# 1-Schematic.net
KiCad netlist of a schematic drawn in EasyEDA
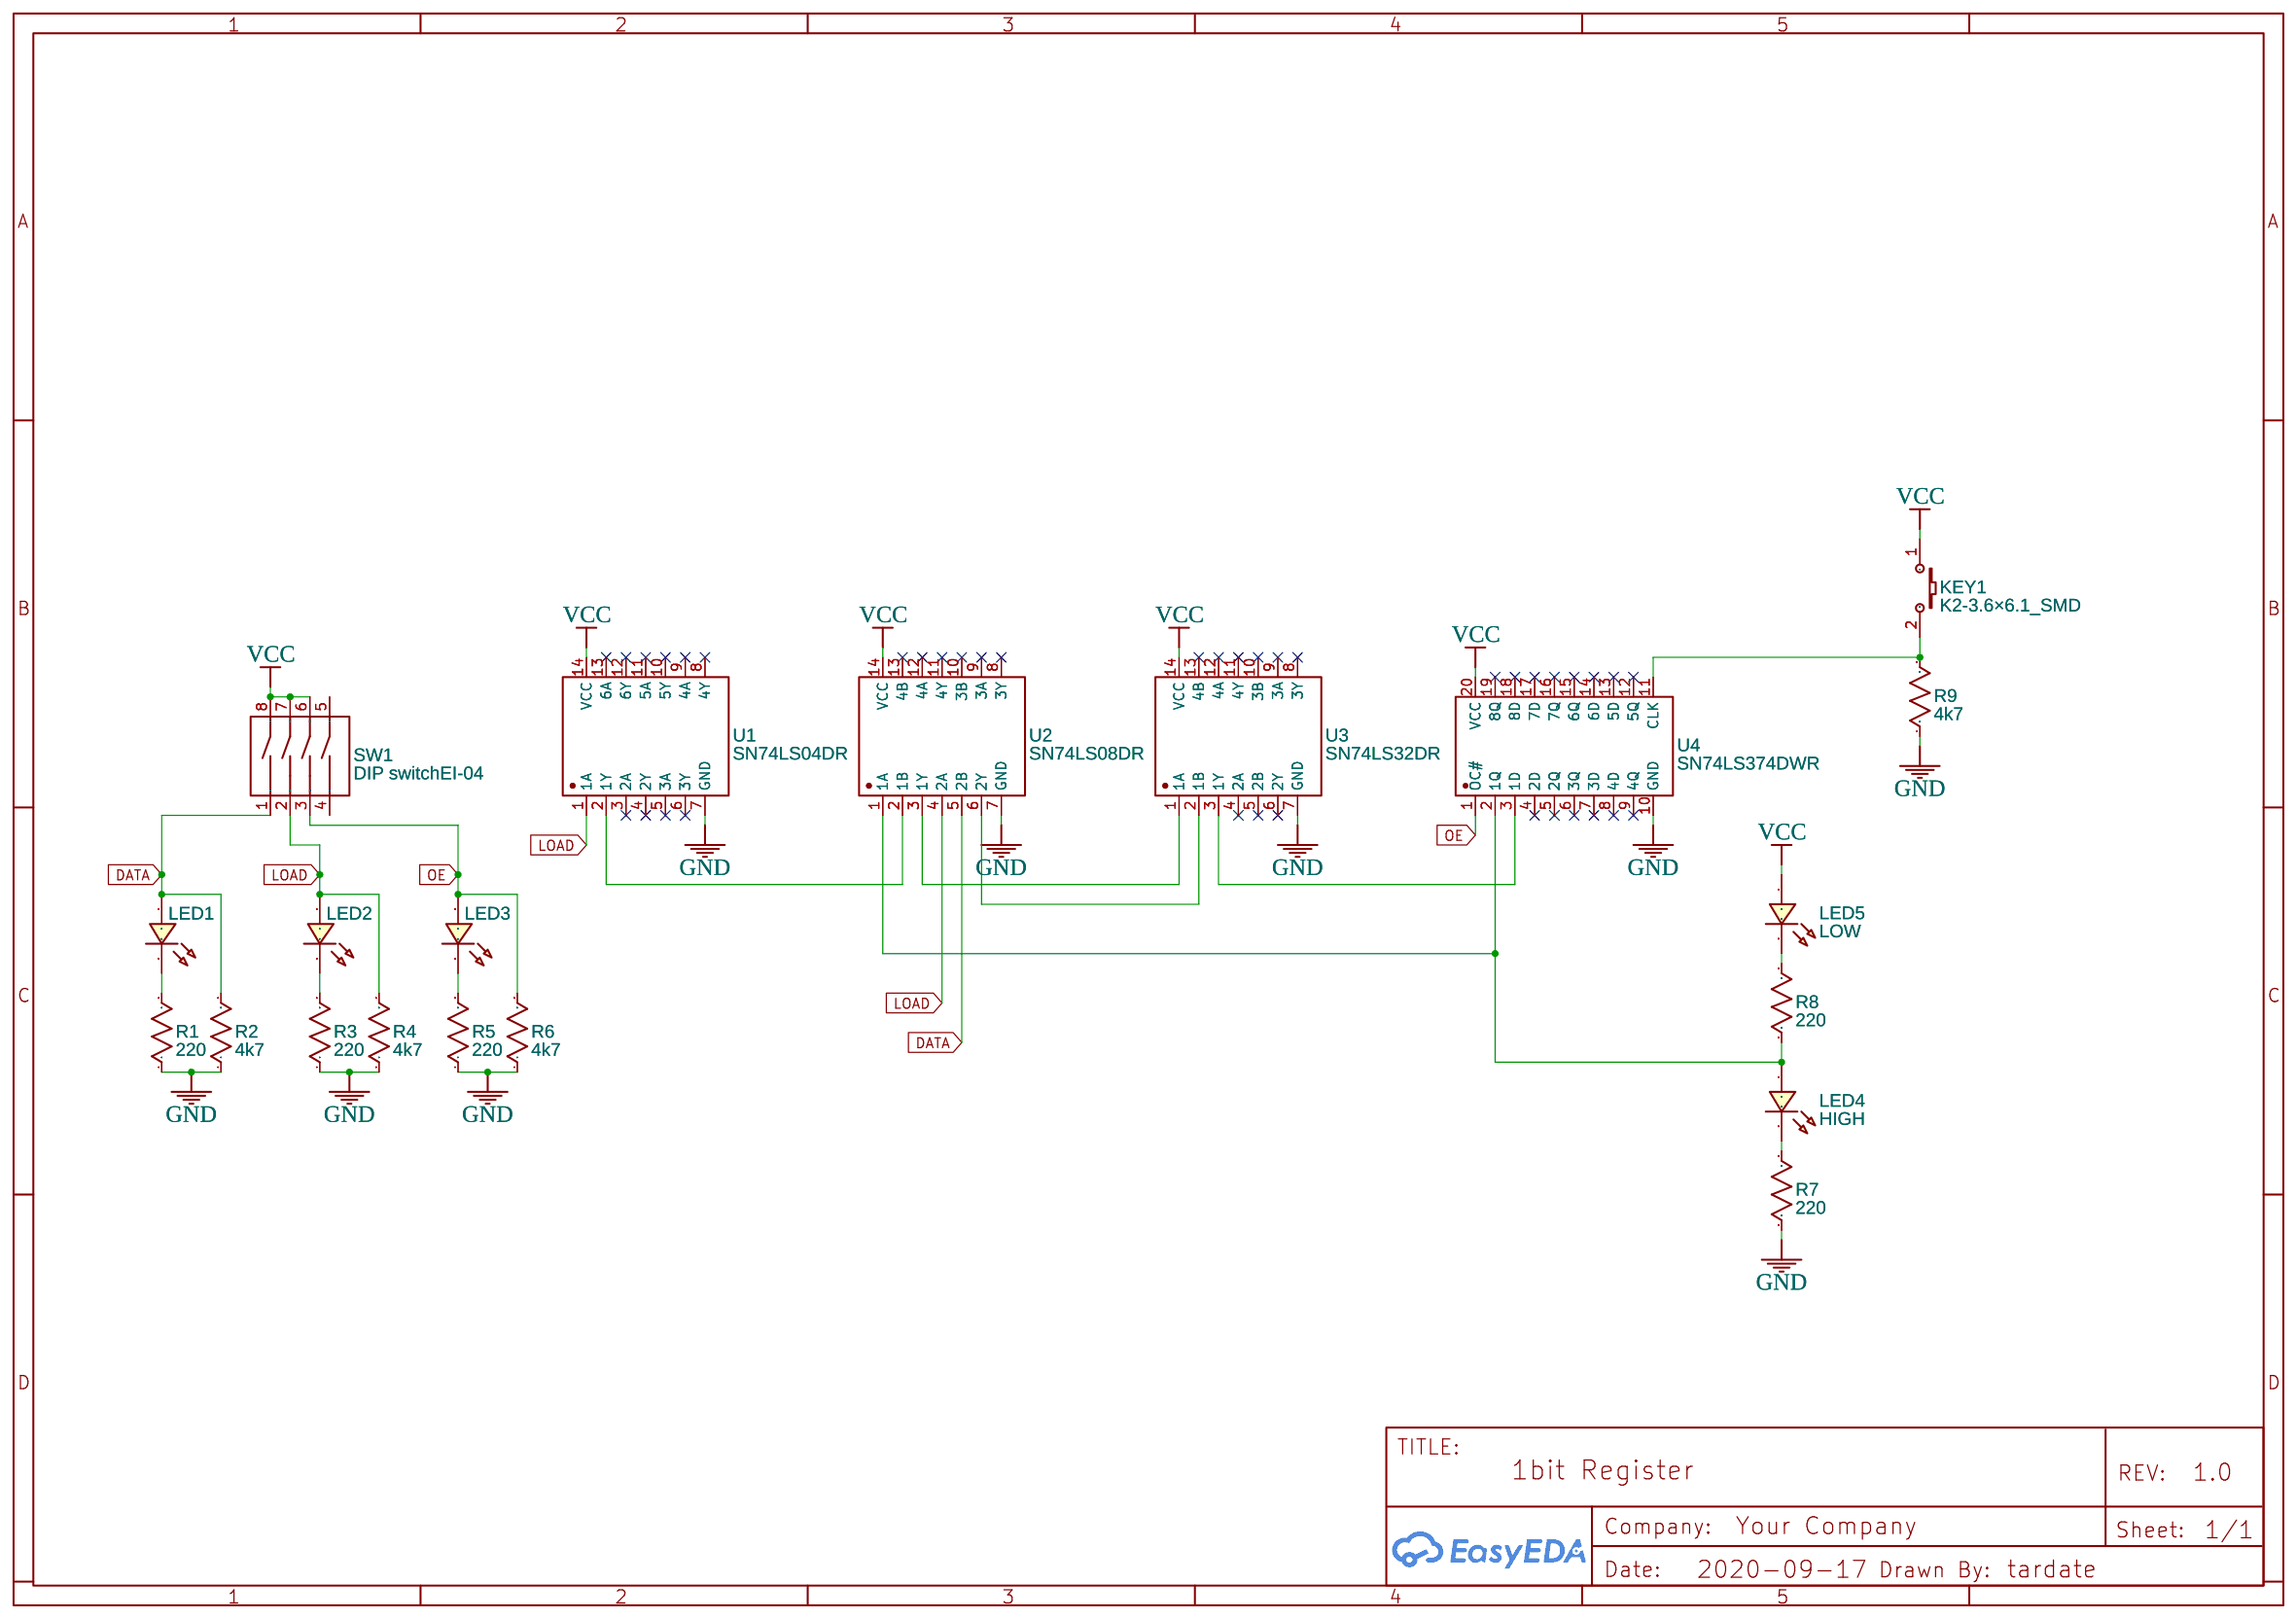
[diagram p0: schematic sheet]

(export (version "E")
  (design (tool "Eeschema 10.0.6"))
  (components
    (comp (ref "KEY1")
      (value "K2-3.6×6.1_SMD")
      (fields
        (field (name "BOM_Manufacturer Part") "K2-1107ST-A4SW-06")
        (field (name "BOM_Supplier Part") "C118141")
      )
      (libsource (lib "") (part "K2-3.6×6.1_SMD"))
    )
    (comp (ref "LED1")
      (value "LED-0603_R")
      (fields
        (field (name "BOM_Manufacturer Part") "19-217/R6C-AL1M2VY/3T")
        (field (name "BOM_Supplier Part") "C72044")
      )
      (libsource (lib "") (part "LED-0603_R"))
    )
    (comp (ref "LED2")
      (value "LED-0603_R")
      (fields
        (field (name "BOM_Manufacturer Part") "19-217/R6C-AL1M2VY/3T")
        (field (name "BOM_Supplier Part") "C72044")
      )
      (libsource (lib "") (part "LED-0603_R"))
    )
    (comp (ref "LED3")
      (value "LED-0603_R")
      (fields
        (field (name "BOM_Manufacturer Part") "19-217/R6C-AL1M2VY/3T")
        (field (name "BOM_Supplier Part") "C72044")
      )
      (libsource (lib "") (part "LED-0603_R"))
    )
    (comp (ref "LED4")
      (value "HIGH")
      (fields
        (field (name "BOM_Manufacturer Part") "19-217/R6C-AL1M2VY/3T")
        (field (name "BOM_Supplier Part") "C72044")
      )
      (libsource (lib "") (part "LED-0603_R"))
    )
    (comp (ref "LED5")
      (value "LOW")
      (fields
        (field (name "BOM_Manufacturer Part") "19-217/R6C-AL1M2VY/3T")
        (field (name "BOM_Supplier Part") "C72044")
      )
      (libsource (lib "") (part "LED-0603_R"))
    )
    (comp (ref "R1") (value "220") (libsource (lib "") (part "R_0603_US")))
    (comp (ref "R2") (value "4k7") (libsource (lib "") (part "R_0603_US")))
    (comp (ref "R3") (value "220") (libsource (lib "") (part "R_0603_US")))
    (comp (ref "R4") (value "4k7") (libsource (lib "") (part "R_0603_US")))
    (comp (ref "R5") (value "220") (libsource (lib "") (part "R_0603_US")))
    (comp (ref "R6") (value "4k7") (libsource (lib "") (part "R_0603_US")))
    (comp (ref "R7") (value "220") (libsource (lib "") (part "R_0603_US")))
    (comp (ref "R8") (value "220") (libsource (lib "") (part "R_0603_US")))
    (comp (ref "R9") (value "4k7") (libsource (lib "") (part "R_0603_US")))
    (comp (ref "SW1")
      (value "DIP switchEI-04")
      (fields (field (name "BOM_Supplier Part") "C99987"))
      (libsource (lib "") (part "DIP switchEI-04"))
    )
    (comp (ref "U1")
      (value "SN74LS04DR")
      (fields (field (name "BOM_Supplier Part") "C6796"))
      (libsource (lib "") (part "SN74LS04DR"))
    )
    (comp (ref "U2")
      (value "SN74LS08DR")
      (fields (field (name "BOM_Supplier Part") "C6802"))
      (libsource (lib "") (part "SN74LS08DR"))
    )
    (comp (ref "U3")
      (value "SN74LS32DR")
      (fields (field (name "BOM_Supplier Part") "C116812"))
      (libsource (lib "") (part "SN74LS32DR"))
    )
    (comp (ref "U4")
      (value "SN74LS374DWR")
      (fields (field (name "BOM_Supplier Part") "C7763"))
      (libsource (lib "") (part "SN74LS374DWR"))
    )
  )
  (nets
    (net (code "1") (name "DATA") (class "Default")
      (node (ref "LED1") (pin "1") (pinfunction "1_1") (pintype "unspecified"))
      (node (ref "R2") (pin "2") (pinfunction "2_2") (pintype "unspecified"))
      (node (ref "SW1") (pin "1") (pinfunction "1_1") (pintype "unspecified"))
      (node (ref "U2") (pin "5") (pinfunction "2B_5") (pintype "unspecified"))
    )
    (net (code "2") (name "GND") (class "Default")
      (node (ref "R1") (pin "1") (pinfunction "1_1") (pintype "unspecified"))
      (node (ref "R2") (pin "1") (pinfunction "1_1") (pintype "unspecified"))
      (node (ref "R3") (pin "1") (pinfunction "1_1") (pintype "unspecified"))
      (node (ref "R4") (pin "1") (pinfunction "1_1") (pintype "unspecified"))
      (node (ref "R5") (pin "1") (pinfunction "1_1") (pintype "unspecified"))
      (node (ref "R6") (pin "1") (pinfunction "1_1") (pintype "unspecified"))
      (node (ref "R7") (pin "1") (pinfunction "1_1") (pintype "unspecified"))
      (node (ref "R9") (pin "1") (pinfunction "1_1") (pintype "unspecified"))
      (node (ref "U1") (pin "7") (pinfunction "GND_7") (pintype "unspecified"))
      (node (ref "U2") (pin "7") (pinfunction "GND_7") (pintype "unspecified"))
      (node (ref "U3") (pin "7") (pinfunction "GND_7") (pintype "unspecified"))
      (node (ref "U4") (pin "10") (pinfunction "GND_10") (pintype "unspecified"))
    )
    (net (code "3") (name "LOAD") (class "Default")
      (node (ref "LED2") (pin "1") (pinfunction "1_1") (pintype "unspecified"))
      (node (ref "R4") (pin "2") (pinfunction "2_2") (pintype "unspecified"))
      (node (ref "SW1") (pin "2") (pinfunction "2_2") (pintype "unspecified"))
      (node (ref "U1") (pin "1") (pinfunction "1A_1") (pintype "unspecified"))
      (node (ref "U2") (pin "4") (pinfunction "2A_4") (pintype "unspecified"))
    )
    (net (code "4") (name "Net-(LED1-Pad2)") (class "Default")
      (node (ref "LED1") (pin "2") (pinfunction "2_2") (pintype "unspecified"))
      (node (ref "R1") (pin "2") (pinfunction "2_2") (pintype "unspecified"))
    )
    (net (code "5") (name "Net-(LED2-Pad2)") (class "Default")
      (node (ref "LED2") (pin "2") (pinfunction "2_2") (pintype "unspecified"))
      (node (ref "R3") (pin "2") (pinfunction "2_2") (pintype "unspecified"))
    )
    (net (code "6") (name "Net-(LED3-Pad2)") (class "Default")
      (node (ref "LED3") (pin "2") (pinfunction "2_2") (pintype "unspecified"))
      (node (ref "R5") (pin "2") (pinfunction "2_2") (pintype "unspecified"))
    )
    (net (code "7") (name "Net-(LED4-Pad2)") (class "Default")
      (node (ref "LED4") (pin "2") (pinfunction "2_2") (pintype "unspecified"))
      (node (ref "R7") (pin "2") (pinfunction "2_2") (pintype "unspecified"))
    )
    (net (code "8") (name "Net-(LED5-Pad2)") (class "Default")
      (node (ref "LED5") (pin "2") (pinfunction "2_2") (pintype "unspecified"))
      (node (ref "R8") (pin "2") (pinfunction "2_2") (pintype "unspecified"))
    )
    (net (code "9") (name "Net-(U1-1Y)") (class "Default")
      (node (ref "U1") (pin "2") (pinfunction "1Y_2") (pintype "unspecified"))
      (node (ref "U2") (pin "2") (pinfunction "1B_2") (pintype "unspecified"))
    )
    (net (code "10") (name "Net-(U2-1A)") (class "Default")
      (node (ref "LED4") (pin "1") (pinfunction "1_1") (pintype "unspecified"))
      (node (ref "R8") (pin "1") (pinfunction "1_1") (pintype "unspecified"))
      (node (ref "U2") (pin "1") (pinfunction "1A_1") (pintype "unspecified"))
      (node (ref "U4") (pin "2") (pinfunction "1Q_2") (pintype "unspecified"))
    )
    (net (code "11") (name "Net-(U2-1Y)") (class "Default")
      (node (ref "U2") (pin "3") (pinfunction "1Y_3") (pintype "unspecified"))
      (node (ref "U3") (pin "1") (pinfunction "1A_1") (pintype "unspecified"))
    )
    (net (code "12") (name "Net-(U2-2Y)") (class "Default")
      (node (ref "U2") (pin "6") (pinfunction "2Y_6") (pintype "unspecified"))
      (node (ref "U3") (pin "2") (pinfunction "1B_2") (pintype "unspecified"))
    )
    (net (code "13") (name "Net-(U3-1Y)") (class "Default")
      (node (ref "U3") (pin "3") (pinfunction "1Y_3") (pintype "unspecified"))
      (node (ref "U4") (pin "3") (pinfunction "1D_3") (pintype "unspecified"))
    )
    (net (code "14") (name "Net-(U4-CLK)") (class "Default")
      (node (ref "KEY1") (pin "2") (pinfunction "2_2") (pintype "unspecified"))
      (node (ref "R9") (pin "2") (pinfunction "2_2") (pintype "unspecified"))
      (node (ref "U4") (pin "11") (pinfunction "CLK_11") (pintype "unspecified"))
    )
    (net (code "15") (name "OE") (class "Default")
      (node (ref "LED3") (pin "1") (pinfunction "1_1") (pintype "unspecified"))
      (node (ref "R6") (pin "2") (pinfunction "2_2") (pintype "unspecified"))
      (node (ref "SW1") (pin "3") (pinfunction "3_3") (pintype "unspecified"))
      (node (ref "U4") (pin "1") (pinfunction "OC#_1") (pintype "unspecified"))
    )
    (net (code "16") (name "VCC") (class "Default")
      (node (ref "KEY1") (pin "1") (pinfunction "1_1") (pintype "unspecified"))
      (node (ref "LED5") (pin "1") (pinfunction "1_1") (pintype "unspecified"))
      (node (ref "SW1") (pin "6") (pinfunction "6_6") (pintype "unspecified"))
      (node (ref "SW1") (pin "7") (pinfunction "7_7") (pintype "unspecified"))
      (node (ref "SW1") (pin "8") (pinfunction "8_8") (pintype "unspecified"))
      (node (ref "U1") (pin "14") (pinfunction "VCC_14") (pintype "unspecified"))
      (node (ref "U2") (pin "14") (pinfunction "VCC_14") (pintype "unspecified"))
      (node (ref "U3") (pin "14") (pinfunction "VCC_14") (pintype "unspecified"))
      (node (ref "U4") (pin "20") (pinfunction "VCC_20") (pintype "unspecified"))
    )
    (net (code "17") (name "unconnected-(SW1-Pad4)") (class "Default")
      (node (ref "SW1") (pin "4") (pinfunction "4_4") (pintype "unspecified"))
    )
    (net (code "18") (name "unconnected-(SW1-Pad5)") (class "Default")
      (node (ref "SW1") (pin "5") (pinfunction "5_5") (pintype "unspecified"))
    )
    (net (code "19") (name "unconnected-(U1-2A-Pad3)") (class "Default")
      (node (ref "U1") (pin "3") (pinfunction "2A_3") (pintype "unspecified+no_connect"))
    )
    (net (code "20") (name "unconnected-(U1-2Y-Pad4)") (class "Default")
      (node (ref "U1") (pin "4") (pinfunction "2Y_4") (pintype "unspecified+no_connect"))
    )
    (net (code "21") (name "unconnected-(U1-3A-Pad5)") (class "Default")
      (node (ref "U1") (pin "5") (pinfunction "3A_5") (pintype "unspecified+no_connect"))
    )
    (net (code "22") (name "unconnected-(U1-3Y-Pad6)") (class "Default")
      (node (ref "U1") (pin "6") (pinfunction "3Y_6") (pintype "unspecified+no_connect"))
    )
    (net (code "23") (name "unconnected-(U1-4A-Pad9)") (class "Default")
      (node (ref "U1") (pin "9") (pinfunction "4A_9") (pintype "unspecified+no_connect"))
    )
    (net (code "24") (name "unconnected-(U1-4Y-Pad8)") (class "Default")
      (node (ref "U1") (pin "8") (pinfunction "4Y_8") (pintype "unspecified+no_connect"))
    )
    (net (code "25") (name "unconnected-(U1-5A-Pad11)") (class "Default")
      (node (ref "U1") (pin "11") (pinfunction "5A_11") (pintype "unspecified+no_connect"))
    )
    (net (code "26") (name "unconnected-(U1-5Y-Pad10)") (class "Default")
      (node (ref "U1") (pin "10") (pinfunction "5Y_10") (pintype "unspecified+no_connect"))
    )
    (net (code "27") (name "unconnected-(U1-6A-Pad13)") (class "Default")
      (node (ref "U1") (pin "13") (pinfunction "6A_13") (pintype "unspecified+no_connect"))
    )
    (net (code "28") (name "unconnected-(U1-6Y-Pad12)") (class "Default")
      (node (ref "U1") (pin "12") (pinfunction "6Y_12") (pintype "unspecified+no_connect"))
    )
    (net (code "29") (name "unconnected-(U2-3A-Pad9)") (class "Default")
      (node (ref "U2") (pin "9") (pinfunction "3A_9") (pintype "unspecified+no_connect"))
    )
    (net (code "30") (name "unconnected-(U2-3B-Pad10)") (class "Default")
      (node (ref "U2") (pin "10") (pinfunction "3B_10") (pintype "unspecified+no_connect"))
    )
    (net (code "31") (name "unconnected-(U2-3Y-Pad8)") (class "Default")
      (node (ref "U2") (pin "8") (pinfunction "3Y_8") (pintype "unspecified+no_connect"))
    )
    (net (code "32") (name "unconnected-(U2-4A-Pad12)") (class "Default")
      (node (ref "U2") (pin "12") (pinfunction "4A_12") (pintype "unspecified+no_connect"))
    )
    (net (code "33") (name "unconnected-(U2-4B-Pad13)") (class "Default")
      (node (ref "U2") (pin "13") (pinfunction "4B_13") (pintype "unspecified+no_connect"))
    )
    (net (code "34") (name "unconnected-(U2-4Y-Pad11)") (class "Default")
      (node (ref "U2") (pin "11") (pinfunction "4Y_11") (pintype "unspecified+no_connect"))
    )
    (net (code "35") (name "unconnected-(U3-2A-Pad4)") (class "Default")
      (node (ref "U3") (pin "4") (pinfunction "2A_4") (pintype "unspecified+no_connect"))
    )
    (net (code "36") (name "unconnected-(U3-2B-Pad5)") (class "Default")
      (node (ref "U3") (pin "5") (pinfunction "2B_5") (pintype "unspecified+no_connect"))
    )
    (net (code "37") (name "unconnected-(U3-2Y-Pad6)") (class "Default")
      (node (ref "U3") (pin "6") (pinfunction "2Y_6") (pintype "unspecified+no_connect"))
    )
    (net (code "38") (name "unconnected-(U3-3A-Pad9)") (class "Default")
      (node (ref "U3") (pin "9") (pinfunction "3A_9") (pintype "unspecified+no_connect"))
    )
    (net (code "39") (name "unconnected-(U3-3B-Pad10)") (class "Default")
      (node (ref "U3") (pin "10") (pinfunction "3B_10") (pintype "unspecified+no_connect"))
    )
    (net (code "40") (name "unconnected-(U3-3Y-Pad8)") (class "Default")
      (node (ref "U3") (pin "8") (pinfunction "3Y_8") (pintype "unspecified+no_connect"))
    )
    (net (code "41") (name "unconnected-(U3-4A-Pad12)") (class "Default")
      (node (ref "U3") (pin "12") (pinfunction "4A_12") (pintype "unspecified+no_connect"))
    )
    (net (code "42") (name "unconnected-(U3-4B-Pad13)") (class "Default")
      (node (ref "U3") (pin "13") (pinfunction "4B_13") (pintype "unspecified+no_connect"))
    )
    (net (code "43") (name "unconnected-(U3-4Y-Pad11)") (class "Default")
      (node (ref "U3") (pin "11") (pinfunction "4Y_11") (pintype "unspecified+no_connect"))
    )
    (net (code "44") (name "unconnected-(U4-2D-Pad4)") (class "Default")
      (node (ref "U4") (pin "4") (pinfunction "2D_4") (pintype "unspecified+no_connect"))
    )
    (net (code "45") (name "unconnected-(U4-2Q-Pad5)") (class "Default")
      (node (ref "U4") (pin "5") (pinfunction "2Q_5") (pintype "unspecified+no_connect"))
    )
    (net (code "46") (name "unconnected-(U4-3D-Pad7)") (class "Default")
      (node (ref "U4") (pin "7") (pinfunction "3D_7") (pintype "unspecified+no_connect"))
    )
    (net (code "47") (name "unconnected-(U4-3Q-Pad6)") (class "Default")
      (node (ref "U4") (pin "6") (pinfunction "3Q_6") (pintype "unspecified+no_connect"))
    )
    (net (code "48") (name "unconnected-(U4-4D-Pad8)") (class "Default")
      (node (ref "U4") (pin "8") (pinfunction "4D_8") (pintype "unspecified+no_connect"))
    )
    (net (code "49") (name "unconnected-(U4-4Q-Pad9)") (class "Default")
      (node (ref "U4") (pin "9") (pinfunction "4Q_9") (pintype "unspecified+no_connect"))
    )
    (net (code "50") (name "unconnected-(U4-5D-Pad13)") (class "Default")
      (node (ref "U4") (pin "13") (pinfunction "5D_13") (pintype "unspecified+no_connect"))
    )
    (net (code "51") (name "unconnected-(U4-5Q-Pad12)") (class "Default")
      (node (ref "U4") (pin "12") (pinfunction "5Q_12") (pintype "unspecified+no_connect"))
    )
    (net (code "52") (name "unconnected-(U4-6D-Pad14)") (class "Default")
      (node (ref "U4") (pin "14") (pinfunction "6D_14") (pintype "unspecified+no_connect"))
    )
    (net (code "53") (name "unconnected-(U4-6Q-Pad15)") (class "Default")
      (node (ref "U4") (pin "15") (pinfunction "6Q_15") (pintype "unspecified+no_connect"))
    )
    (net (code "54") (name "unconnected-(U4-7D-Pad17)") (class "Default")
      (node (ref "U4") (pin "17") (pinfunction "7D_17") (pintype "unspecified+no_connect"))
    )
    (net (code "55") (name "unconnected-(U4-7Q-Pad16)") (class "Default")
      (node (ref "U4") (pin "16") (pinfunction "7Q_16") (pintype "unspecified+no_connect"))
    )
    (net (code "56") (name "unconnected-(U4-8D-Pad18)") (class "Default")
      (node (ref "U4") (pin "18") (pinfunction "8D_18") (pintype "unspecified+no_connect"))
    )
    (net (code "57") (name "unconnected-(U4-8Q-Pad19)") (class "Default")
      (node (ref "U4") (pin "19") (pinfunction "8Q_19") (pintype "unspecified+no_connect"))
    )
  )
)
